# E17-PDU-LOAD_1.net
KiCad netlist of a schematic drawn in Altium Designer
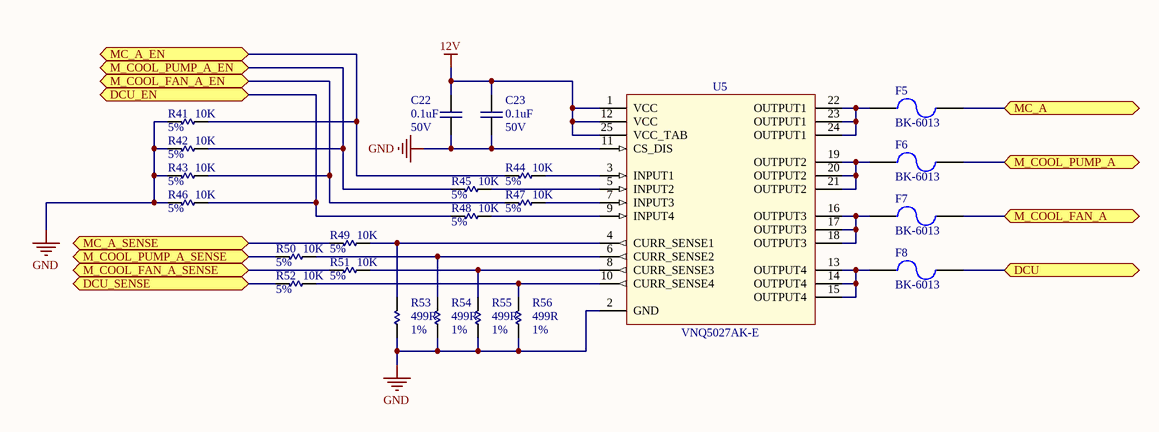
[diagram p0: E17-PDU-LOAD_1.SchDoc]

(export (version "E")
  (design (tool "Eeschema 10.0.6"))
  (components
    (comp (ref "C22")
      (value "0.1uF")
      (footprint "C0805")
      (description "Generic 0805 Capacitor")
      (fields
        (field (name "TOLERANCE") "10%")
        (field (name "VOLTAGE") "50V")
        (field (name "Comment") "C_0805_Generic")
      )
      (libsource (lib "Compiled_PDU") (part "C_0805_Generic"))
    )
    (comp (ref "C23")
      (value "0.1uF")
      (footprint "C0805")
      (description "Generic 0805 Capacitor")
      (fields
        (field (name "TOLERANCE") "10%")
        (field (name "VOLTAGE") "50V")
        (field (name "Comment") "C_0805_Generic")
      )
      (libsource (lib "Compiled_PDU") (part "C_0805_Generic"))
    )
    (comp (ref "F5")
      (value "F_BK-6013")
      (footprint "BK-6013")
      (description "FUSE HOLDER BLADE PCB")
      (fields (field (name "MFG") "MPD") (field (name "MFG_PN") "BK-6013"))
      (libsource (lib "Compiled_PDU") (part "F_BK-6013"))
    )
    (comp (ref "F6")
      (value "F_BK-6013")
      (footprint "BK-6013")
      (description "FUSE HOLDER BLADE PCB")
      (fields (field (name "MFG") "MPD") (field (name "MFG_PN") "BK-6013"))
      (libsource (lib "Compiled_PDU") (part "F_BK-6013"))
    )
    (comp (ref "F7")
      (value "F_BK-6013")
      (footprint "BK-6013")
      (description "FUSE HOLDER BLADE PCB")
      (fields (field (name "MFG") "MPD") (field (name "MFG_PN") "BK-6013"))
      (libsource (lib "Compiled_PDU") (part "F_BK-6013"))
    )
    (comp (ref "F8")
      (value "F_BK-6013")
      (footprint "BK-6013")
      (description "FUSE HOLDER BLADE PCB")
      (fields (field (name "MFG") "MPD") (field (name "MFG_PN") "BK-6013"))
      (libsource (lib "Compiled_PDU") (part "F_BK-6013"))
    )
    (comp (ref "R41")
      (value "10K")
      (footprint "R0603")
      (description "Generic 0603 Resistor")
      (fields
        (field (name "POWER") "1/10W")
        (field (name "TOLERANCE") "5%")
        (field (name "Comment") "R_0603_Generic")
      )
      (libsource (lib "Compiled_PDU") (part "R_0603_Generic"))
    )
    (comp (ref "R42")
      (value "10K")
      (footprint "R0603")
      (description "Generic 0603 Resistor")
      (fields
        (field (name "POWER") "1/10W")
        (field (name "TOLERANCE") "5%")
        (field (name "Comment") "R_0603_Generic")
      )
      (libsource (lib "Compiled_PDU") (part "R_0603_Generic"))
    )
    (comp (ref "R43")
      (value "10K")
      (footprint "R0603")
      (description "Generic 0603 Resistor")
      (fields
        (field (name "POWER") "1/10W")
        (field (name "TOLERANCE") "5%")
        (field (name "Comment") "R_0603_Generic")
      )
      (libsource (lib "Compiled_PDU") (part "R_0603_Generic"))
    )
    (comp (ref "R44")
      (value "10K")
      (footprint "R0603")
      (description "Generic 0603 Resistor")
      (fields
        (field (name "POWER") "1/10W")
        (field (name "TOLERANCE") "5%")
        (field (name "Comment") "R_0603_Generic")
      )
      (libsource (lib "Compiled_PDU") (part "R_0603_Generic"))
    )
    (comp (ref "R45")
      (value "10K")
      (footprint "R0603")
      (description "Generic 0603 Resistor")
      (fields
        (field (name "POWER") "1/10W")
        (field (name "TOLERANCE") "5%")
        (field (name "Comment") "R_0603_Generic")
      )
      (libsource (lib "Compiled_PDU") (part "R_0603_Generic"))
    )
    (comp (ref "R46")
      (value "10K")
      (footprint "R0603")
      (description "Generic 0603 Resistor")
      (fields
        (field (name "POWER") "1/10W")
        (field (name "TOLERANCE") "5%")
        (field (name "Comment") "R_0603_Generic")
      )
      (libsource (lib "Compiled_PDU") (part "R_0603_Generic"))
    )
    (comp (ref "R47")
      (value "10K")
      (footprint "R0603")
      (description "Generic 0603 Resistor")
      (fields
        (field (name "POWER") "1/10W")
        (field (name "TOLERANCE") "5%")
        (field (name "Comment") "R_0603_Generic")
      )
      (libsource (lib "Compiled_PDU") (part "R_0603_Generic"))
    )
    (comp (ref "R48")
      (value "10K")
      (footprint "R0603")
      (description "Generic 0603 Resistor")
      (fields
        (field (name "POWER") "1/10W")
        (field (name "TOLERANCE") "5%")
        (field (name "Comment") "R_0603_Generic")
      )
      (libsource (lib "Compiled_PDU") (part "R_0603_Generic"))
    )
    (comp (ref "R49")
      (value "10K")
      (footprint "R0603")
      (description "Generic 0603 Resistor")
      (fields
        (field (name "POWER") "1/10W")
        (field (name "TOLERANCE") "5%")
        (field (name "Comment") "R_0603_Generic")
      )
      (libsource (lib "Compiled_PDU") (part "R_0603_Generic"))
    )
    (comp (ref "R50")
      (value "10K")
      (footprint "R0603")
      (description "Generic 0603 Resistor")
      (fields
        (field (name "POWER") "1/10W")
        (field (name "TOLERANCE") "5%")
        (field (name "Comment") "R_0603_Generic")
      )
      (libsource (lib "Compiled_PDU") (part "R_0603_Generic"))
    )
    (comp (ref "R51")
      (value "10K")
      (footprint "R0603")
      (description "Generic 0603 Resistor")
      (fields
        (field (name "POWER") "1/10W")
        (field (name "TOLERANCE") "5%")
        (field (name "Comment") "R_0603_Generic")
      )
      (libsource (lib "Compiled_PDU") (part "R_0603_Generic"))
    )
    (comp (ref "R52")
      (value "10K")
      (footprint "R0603")
      (description "Generic 0603 Resistor")
      (fields
        (field (name "POWER") "1/10W")
        (field (name "TOLERANCE") "5%")
        (field (name "Comment") "R_0603_Generic")
      )
      (libsource (lib "Compiled_PDU") (part "R_0603_Generic"))
    )
    (comp (ref "R53")
      (value "499R")
      (footprint "R0603")
      (description "Generic 0603 Resistor")
      (fields
        (field (name "POWER") "1/8W")
        (field (name "TOLERANCE") "1%")
        (field (name "Comment") "R_0603_Generic")
      )
      (libsource (lib "Compiled_PDU") (part "R_0603_Generic"))
    )
    (comp (ref "R54")
      (value "499R")
      (footprint "R0603")
      (description "Generic 0603 Resistor")
      (fields
        (field (name "POWER") "1/8W")
        (field (name "TOLERANCE") "1%")
        (field (name "Comment") "R_0603_Generic")
      )
      (libsource (lib "Compiled_PDU") (part "R_0603_Generic"))
    )
    (comp (ref "R55")
      (value "499R")
      (footprint "R0603")
      (description "Generic 0603 Resistor")
      (fields
        (field (name "POWER") "1/8W")
        (field (name "TOLERANCE") "1%")
        (field (name "Comment") "R_0603_Generic")
      )
      (libsource (lib "Compiled_PDU") (part "R_0603_Generic"))
    )
    (comp (ref "R56")
      (value "499R")
      (footprint "R0603")
      (description "Generic 0603 Resistor")
      (fields
        (field (name "POWER") "1/8W")
        (field (name "TOLERANCE") "1%")
        (field (name "Comment") "R_0603_Generic")
      )
      (libsource (lib "Compiled_PDU") (part "R_0603_Generic"))
    )
    (comp (ref "U5")
      (value "U_VNQ5027AK-E")
      (footprint "PowerSSO-24")
      (description "LOAD CHANNEL HIGH SIDE 42A 4 Channel")
      (fields (field (name "MFG") "STmicroelectronics") (field (name "MFG_PN") "VNQ5027AK-E"))
      (libsource (lib "Compiled_PDU") (part "U_VNQ5027AK-E"))
    )
  )
  (nets
    (net (code "1") (name "/DCU") (class "Default")
      (node (ref "F8") (pin "2") (pinfunction "2_2") (pintype "passive"))
    )
    (net (code "2") (name "/DCU_EN") (class "Default")
      (node (ref "R46") (pin "2") (pinfunction "2_2") (pintype "passive"))
      (node (ref "R48") (pin "1") (pinfunction "1_1") (pintype "passive"))
    )
    (net (code "3") (name "/DCU_SENSE") (class "Default")
      (node (ref "R52") (pin "1") (pinfunction "1_1") (pintype "passive"))
    )
    (net (code "4") (name "/MC_A") (class "Default")
      (node (ref "F5") (pin "2") (pinfunction "2_2") (pintype "passive"))
    )
    (net (code "5") (name "/MC_A_EN") (class "Default")
      (node (ref "R41") (pin "2") (pinfunction "2_2") (pintype "passive"))
      (node (ref "R44") (pin "1") (pinfunction "1_1") (pintype "passive"))
    )
    (net (code "6") (name "/MC_A_SENSE") (class "Default")
      (node (ref "R49") (pin "1") (pinfunction "1_1") (pintype "passive"))
    )
    (net (code "7") (name "/M_COOL_FAN_A") (class "Default")
      (node (ref "F7") (pin "2") (pinfunction "2_2") (pintype "passive"))
    )
    (net (code "8") (name "/M_COOL_FAN_A_EN") (class "Default")
      (node (ref "R43") (pin "2") (pinfunction "2_2") (pintype "passive"))
      (node (ref "R47") (pin "1") (pinfunction "1_1") (pintype "passive"))
    )
    (net (code "9") (name "/M_COOL_FAN_A_SENSE") (class "Default")
      (node (ref "R51") (pin "1") (pinfunction "1_1") (pintype "passive"))
    )
    (net (code "10") (name "/M_COOL_PUMP_A") (class "Default")
      (node (ref "F6") (pin "2") (pinfunction "2_2") (pintype "passive"))
    )
    (net (code "11") (name "/M_COOL_PUMP_A_EN") (class "Default")
      (node (ref "R42") (pin "2") (pinfunction "2_2") (pintype "passive"))
      (node (ref "R45") (pin "1") (pinfunction "1_1") (pintype "passive"))
    )
    (net (code "12") (name "/M_COOL_PUMP_A_SENSE") (class "Default")
      (node (ref "R50") (pin "1") (pinfunction "1_1") (pintype "passive"))
    )
    (net (code "13") (name "12V") (class "Default")
      (node (ref "C22") (pin "1") (pinfunction "EGND_1") (pintype "passive"))
      (node (ref "C23") (pin "1") (pinfunction "EGND_1") (pintype "passive"))
      (node (ref "U5") (pin "1") (pinfunction "VCC_1") (pintype "power_in"))
      (node (ref "U5") (pin "12") (pinfunction "VCC_12") (pintype "power_in"))
      (node (ref "U5") (pin "25") (pinfunction "VCC_TAB_25") (pintype "power_in"))
    )
    (net (code "14") (name "GND") (class "Default")
      (node (ref "C22") (pin "2") (pinfunction "2_2") (pintype "passive"))
      (node (ref "C23") (pin "2") (pinfunction "2_2") (pintype "passive"))
      (node (ref "R41") (pin "1") (pinfunction "1_1") (pintype "passive"))
      (node (ref "R42") (pin "1") (pinfunction "1_1") (pintype "passive"))
      (node (ref "R43") (pin "1") (pinfunction "1_1") (pintype "passive"))
      (node (ref "R46") (pin "1") (pinfunction "1_1") (pintype "passive"))
      (node (ref "R53") (pin "2") (pinfunction "2_2") (pintype "passive"))
      (node (ref "R54") (pin "2") (pinfunction "2_2") (pintype "passive"))
      (node (ref "R55") (pin "2") (pinfunction "2_2") (pintype "passive"))
      (node (ref "R56") (pin "2") (pinfunction "2_2") (pintype "passive"))
      (node (ref "U5") (pin "11") (pinfunction "CS_DIS_11") (pintype "input"))
      (node (ref "U5") (pin "2") (pinfunction "GND_2") (pintype "power_in"))
    )
    (net (code "15") (name "Net-(F5-Pad1)") (class "Default")
      (node (ref "F5") (pin "1") (pinfunction "1_1") (pintype "passive"))
      (node (ref "U5") (pin "22") (pinfunction "OUTPUT1_22") (pintype "power_in"))
      (node (ref "U5") (pin "23") (pinfunction "OUTPUT1_23") (pintype "power_in"))
      (node (ref "U5") (pin "24") (pinfunction "OUTPUT1_24") (pintype "power_in"))
    )
    (net (code "16") (name "Net-(F6-Pad1)") (class "Default")
      (node (ref "F6") (pin "1") (pinfunction "1_1") (pintype "passive"))
      (node (ref "U5") (pin "19") (pinfunction "OUTPUT2_19") (pintype "power_in"))
      (node (ref "U5") (pin "20") (pinfunction "OUTPUT2_20") (pintype "power_in"))
      (node (ref "U5") (pin "21") (pinfunction "OUTPUT2_21") (pintype "power_in"))
    )
    (net (code "17") (name "Net-(F7-Pad1)") (class "Default")
      (node (ref "F7") (pin "1") (pinfunction "1_1") (pintype "passive"))
      (node (ref "U5") (pin "16") (pinfunction "OUTPUT3_16") (pintype "power_in"))
      (node (ref "U5") (pin "17") (pinfunction "OUTPUT3_17") (pintype "power_in"))
      (node (ref "U5") (pin "18") (pinfunction "OUTPUT3_18") (pintype "power_in"))
    )
    (net (code "18") (name "Net-(F8-Pad1)") (class "Default")
      (node (ref "F8") (pin "1") (pinfunction "1_1") (pintype "passive"))
      (node (ref "U5") (pin "13") (pinfunction "OUTPUT4_13") (pintype "power_in"))
      (node (ref "U5") (pin "14") (pinfunction "OUTPUT4_14") (pintype "power_in"))
      (node (ref "U5") (pin "15") (pinfunction "OUTPUT4_15") (pintype "power_in"))
    )
    (net (code "19") (name "Net-(U5-CURR_SENSE1)") (class "Default")
      (node (ref "R49") (pin "2") (pinfunction "2_2") (pintype "passive"))
      (node (ref "R53") (pin "1") (pinfunction "1_1") (pintype "passive"))
      (node (ref "U5") (pin "4") (pinfunction "CURR_SENSE1_4") (pintype "output"))
    )
    (net (code "20") (name "Net-(U5-CURR_SENSE2)") (class "Default")
      (node (ref "R50") (pin "2") (pinfunction "2_2") (pintype "passive"))
      (node (ref "R54") (pin "1") (pinfunction "1_1") (pintype "passive"))
      (node (ref "U5") (pin "6") (pinfunction "CURR_SENSE2_6") (pintype "output"))
    )
    (net (code "21") (name "Net-(U5-CURR_SENSE3)") (class "Default")
      (node (ref "R51") (pin "2") (pinfunction "2_2") (pintype "passive"))
      (node (ref "R55") (pin "1") (pinfunction "1_1") (pintype "passive"))
      (node (ref "U5") (pin "8") (pinfunction "CURR_SENSE3_8") (pintype "output"))
    )
    (net (code "22") (name "Net-(U5-CURR_SENSE4)") (class "Default")
      (node (ref "R52") (pin "2") (pinfunction "2_2") (pintype "passive"))
      (node (ref "R56") (pin "1") (pinfunction "1_1") (pintype "passive"))
      (node (ref "U5") (pin "10") (pinfunction "CURR_SENSE4_10") (pintype "output"))
    )
    (net (code "23") (name "Net-(U5-INPUT1)") (class "Default")
      (node (ref "R44") (pin "2") (pinfunction "2_2") (pintype "passive"))
      (node (ref "U5") (pin "3") (pinfunction "INPUT1_3") (pintype "input"))
    )
    (net (code "24") (name "Net-(U5-INPUT2)") (class "Default")
      (node (ref "R45") (pin "2") (pinfunction "2_2") (pintype "passive"))
      (node (ref "U5") (pin "5") (pinfunction "INPUT2_5") (pintype "input"))
    )
    (net (code "25") (name "Net-(U5-INPUT3)") (class "Default")
      (node (ref "R47") (pin "2") (pinfunction "2_2") (pintype "passive"))
      (node (ref "U5") (pin "7") (pinfunction "INPUT3_7") (pintype "input"))
    )
    (net (code "26") (name "Net-(U5-INPUT4)") (class "Default")
      (node (ref "R48") (pin "2") (pinfunction "2_2") (pintype "passive"))
      (node (ref "U5") (pin "9") (pinfunction "INPUT4_9") (pintype "input"))
    )
  )
)
